# main_board.net
KiCad netlist of a schematic drawn in Altium Designer
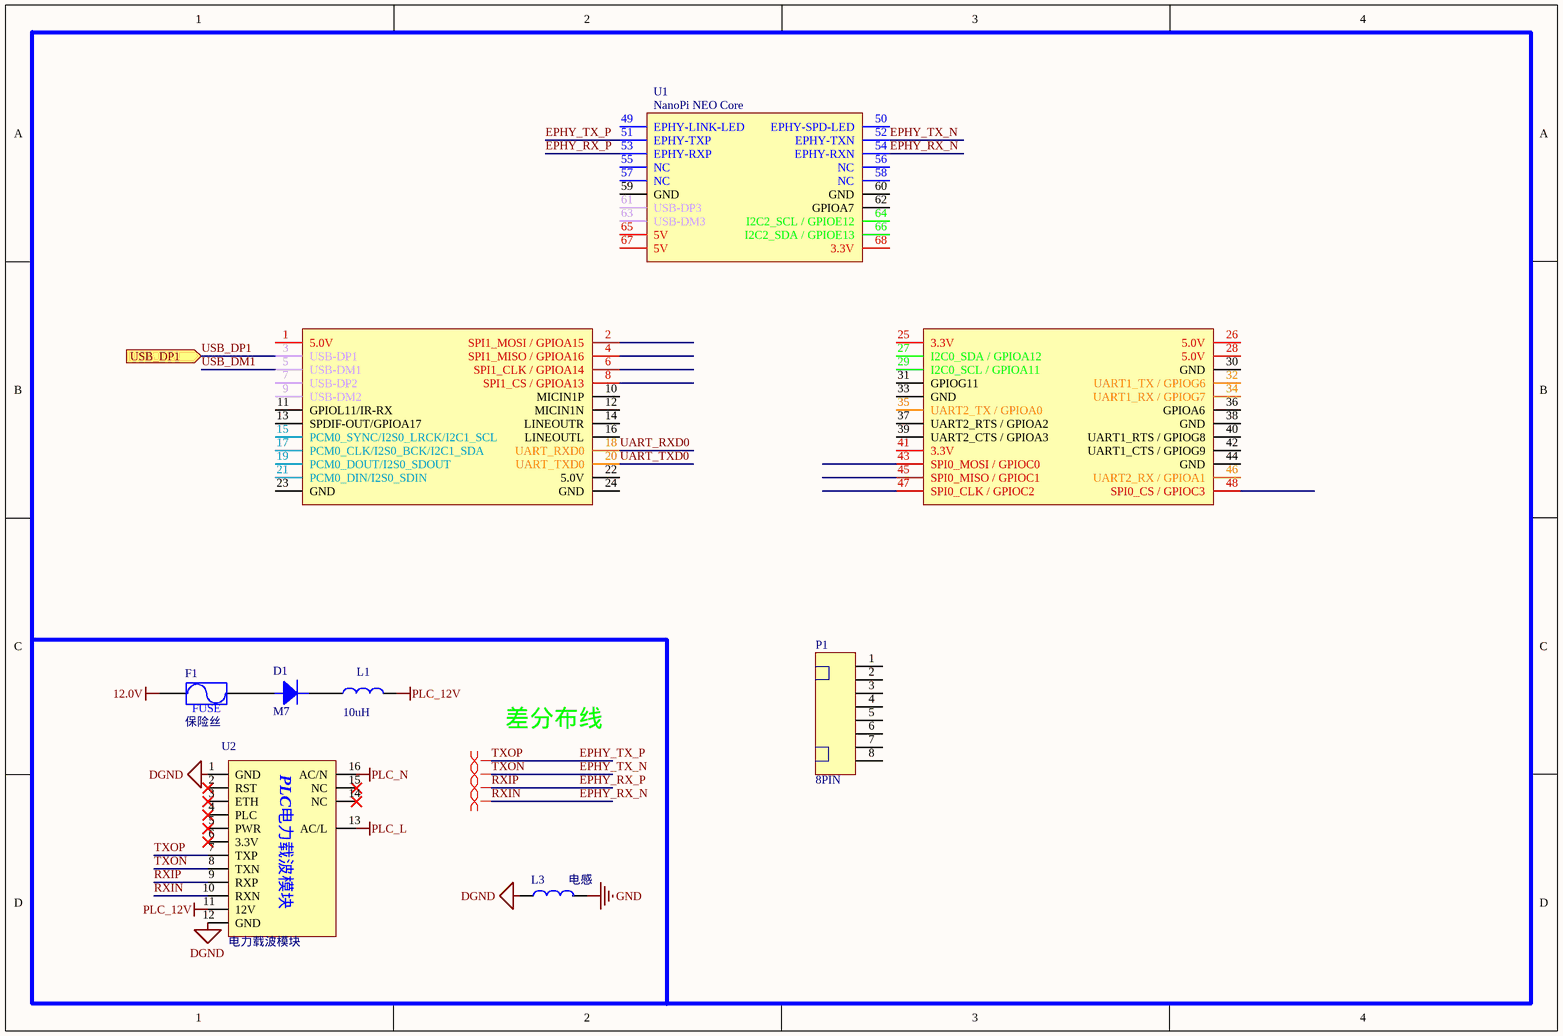
[diagram p0: main_board.SchDoc]

(export (version "E")
  (design (tool "Eeschema 10.0.6"))
  (components
    (comp (ref "D1")
      (value "M7")
      (footprint "SMA/DO-214AC")
      (description "二极管")
      (libsource (lib "集大电协1.5") (part "Diode"))
    )
    (comp (ref "F1") (value "保险丝") (footprint "FUSE-1206") (libsource (lib "集大电协1.2") (part "Fuse")))
    (comp (ref "L1")
      (value "10uH")
      (footprint "1206L")
      (description "电感")
      (libsource (lib "集大电协1.5") (part "L"))
    )
    (comp (ref "L3") (value "电感") (footprint "1206L") (libsource (lib "集大电协1.5") (part "L")))
    (comp (ref "P1") (value "8PIN") (footprint "MX1.25WS-8P") (libsource (lib "MX") (part "MX1.25-8P")))
    (comp (ref "U1")
      (value "NanoPi NEO Core")
      (footprint "NanoPi NEO Core")
      (libsource (lib "集大电协1.5") (part "NanoPi NEO Core"))
    )
    (comp (ref "U2")
      (value "电力载波模块")
      (footprint "电力载波模块6410")
      (libsource (lib "集大电协1.2") (part "电力载波模块6410"))
    )
  )
  (nets
    (net (code "1") (name "/EPHY_RX_N") (class "Default")
      (node (ref "U1") (pin "54") (pinfunction "EPHY-RXN_54") (pintype "passive"))
      (node (ref "U2") (pin "10") (pinfunction "RXN_10") (pintype "passive"))
    )
    (net (code "2") (name "/EPHY_RX_P") (class "Default")
      (node (ref "U1") (pin "53") (pinfunction "EPHY-RXP_53") (pintype "passive"))
      (node (ref "U2") (pin "9") (pinfunction "RXP_9") (pintype "passive"))
    )
    (net (code "3") (name "/EPHY_TX_N") (class "Default")
      (node (ref "U1") (pin "52") (pinfunction "EPHY-TXN_52") (pintype "passive"))
      (node (ref "U2") (pin "8") (pinfunction "TXN_8") (pintype "passive"))
    )
    (net (code "4") (name "/EPHY_TX_P") (class "Default")
      (node (ref "U1") (pin "51") (pinfunction "EPHY-TXP_51") (pintype "passive"))
      (node (ref "U2") (pin "7") (pinfunction "TXP_7") (pintype "passive"))
    )
    (net (code "5") (name "/UART_RXD0") (class "Default")
      (node (ref "U1") (pin "18") (pinfunction "UART_RXD0_18") (pintype "passive"))
    )
    (net (code "6") (name "/UART_TXD0") (class "Default")
      (node (ref "U1") (pin "20") (pinfunction "UART_TXD0_20") (pintype "passive"))
    )
    (net (code "7") (name "/USB_DM1") (class "Default")
      (node (ref "U1") (pin "5") (pinfunction "USB-DM1_5") (pintype "passive"))
    )
    (net (code "8") (name "/USB_DP1") (class "Default")
      (node (ref "U1") (pin "3") (pinfunction "USB-DP1_3") (pintype "passive"))
    )
    (net (code "9") (name "12.0V") (class "Default")
      (node (ref "F1") (pin "1") (pinfunction "1_1") (pintype "passive"))
    )
    (net (code "10") (name "DGND") (class "Default")
      (node (ref "L3") (pin "1") (pinfunction "1_1") (pintype "passive"))
      (node (ref "U2") (pin "1") (pinfunction "GND_1") (pintype "passive"))
      (node (ref "U2") (pin "12") (pinfunction "GND_12") (pintype "passive"))
    )
    (net (code "11") (name "GND") (class "Default")
      (node (ref "L3") (pin "2") (pinfunction "2_2") (pintype "passive"))
    )
    (net (code "12") (name "Net-(D1-Pad1)") (class "Default")
      (node (ref "D1") (pin "1") (pintype "passive"))
      (node (ref "F1") (pin "2") (pinfunction "2_2") (pintype "passive"))
    )
    (net (code "13") (name "Net-(D1-Pad2)") (class "Default")
      (node (ref "D1") (pin "2") (pinfunction "2_2") (pintype "passive"))
      (node (ref "L1") (pin "1") (pinfunction "1_1") (pintype "passive"))
    )
    (net (code "14") (name "PLC_12V") (class "Default")
      (node (ref "L1") (pin "2") (pinfunction "2_2") (pintype "passive"))
      (node (ref "U2") (pin "11") (pinfunction "12V_11") (pintype "passive"))
    )
    (net (code "15") (name "PLC_L") (class "Default")
      (node (ref "U2") (pin "13") (pinfunction "AC/L_13") (pintype "passive"))
    )
    (net (code "16") (name "PLC_N") (class "Default")
      (node (ref "U2") (pin "16") (pinfunction "AC/N_16") (pintype "passive"))
    )
    (net (code "17") (name "unconnected-(P1-Pad1)") (class "Default")
      (node (ref "P1") (pin "1") (pinfunction "1_1") (pintype "passive"))
    )
    (net (code "18") (name "unconnected-(P1-Pad2)") (class "Default")
      (node (ref "P1") (pin "2") (pinfunction "2_2") (pintype "passive"))
    )
    (net (code "19") (name "unconnected-(P1-Pad3)") (class "Default")
      (node (ref "P1") (pin "3") (pinfunction "3_3") (pintype "passive"))
    )
    (net (code "20") (name "unconnected-(P1-Pad4)") (class "Default")
      (node (ref "P1") (pin "4") (pinfunction "4_4") (pintype "passive"))
    )
    (net (code "21") (name "unconnected-(P1-Pad5)") (class "Default")
      (node (ref "P1") (pin "5") (pinfunction "5_5") (pintype "passive"))
    )
    (net (code "22") (name "unconnected-(P1-Pad6)") (class "Default")
      (node (ref "P1") (pin "6") (pinfunction "6_6") (pintype "passive"))
    )
    (net (code "23") (name "unconnected-(P1-Pad7)") (class "Default")
      (node (ref "P1") (pin "7") (pinfunction "7_7") (pintype "passive"))
    )
    (net (code "24") (name "unconnected-(P1-Pad8)") (class "Default")
      (node (ref "P1") (pin "8") (pinfunction "8_8") (pintype "passive"))
    )
    (net (code "25") (name "unconnected-(U1-3.3V-Pad25)") (class "Default")
      (node (ref "U1") (pin "25") (pinfunction "3.3V_25") (pintype "passive"))
    )
    (net (code "26") (name "unconnected-(U1-3.3V-Pad41)") (class "Default")
      (node (ref "U1") (pin "41") (pinfunction "3.3V_41") (pintype "passive"))
    )
    (net (code "27") (name "unconnected-(U1-3.3V-Pad68)") (class "Default")
      (node (ref "U1") (pin "68") (pinfunction "3.3V_68") (pintype "passive"))
    )
    (net (code "28") (name "unconnected-(U1-5.0V-Pad1)") (class "Default")
      (node (ref "U1") (pin "1") (pinfunction "5.0V_1") (pintype "passive"))
    )
    (net (code "29") (name "unconnected-(U1-5.0V-Pad22)") (class "Default")
      (node (ref "U1") (pin "22") (pinfunction "5.0V_22") (pintype "passive"))
    )
    (net (code "30") (name "unconnected-(U1-5.0V-Pad26)") (class "Default")
      (node (ref "U1") (pin "26") (pinfunction "5.0V_26") (pintype "passive"))
    )
    (net (code "31") (name "unconnected-(U1-5.0V-Pad28)") (class "Default")
      (node (ref "U1") (pin "28") (pinfunction "5.0V_28") (pintype "passive"))
    )
    (net (code "32") (name "unconnected-(U1-5V-Pad65)") (class "Default")
      (node (ref "U1") (pin "65") (pinfunction "5V_65") (pintype "passive"))
    )
    (net (code "33") (name "unconnected-(U1-5V-Pad67)") (class "Default")
      (node (ref "U1") (pin "67") (pinfunction "5V_67") (pintype "passive"))
    )
    (net (code "34") (name "unconnected-(U1-EPHY-LINK-LED-Pad49)") (class "Default")
      (node (ref "U1") (pin "49") (pinfunction "EPHY-LINK-LED_49") (pintype "passive"))
    )
    (net (code "35") (name "unconnected-(U1-EPHY-SPD-LED-Pad50)") (class "Default")
      (node (ref "U1") (pin "50") (pinfunction "EPHY-SPD-LED_50") (pintype "passive"))
    )
    (net (code "36") (name "unconnected-(U1-GND-Pad23)") (class "Default")
      (node (ref "U1") (pin "23") (pinfunction "GND_23") (pintype "passive"))
    )
    (net (code "37") (name "unconnected-(U1-GND-Pad24)") (class "Default")
      (node (ref "U1") (pin "24") (pinfunction "GND_24") (pintype "passive"))
    )
    (net (code "38") (name "unconnected-(U1-GND-Pad30)") (class "Default")
      (node (ref "U1") (pin "30") (pinfunction "GND_30") (pintype "passive"))
    )
    (net (code "39") (name "unconnected-(U1-GND-Pad33)") (class "Default")
      (node (ref "U1") (pin "33") (pinfunction "GND_33") (pintype "passive"))
    )
    (net (code "40") (name "unconnected-(U1-GND-Pad38)") (class "Default")
      (node (ref "U1") (pin "38") (pinfunction "GND_38") (pintype "passive"))
    )
    (net (code "41") (name "unconnected-(U1-GND-Pad44)") (class "Default")
      (node (ref "U1") (pin "44") (pinfunction "GND_44") (pintype "passive"))
    )
    (net (code "42") (name "unconnected-(U1-GND-Pad59)") (class "Default")
      (node (ref "U1") (pin "59") (pinfunction "GND_59") (pintype "passive"))
    )
    (net (code "43") (name "unconnected-(U1-GND-Pad60)") (class "Default")
      (node (ref "U1") (pin "60") (pinfunction "GND_60") (pintype "passive"))
    )
    (net (code "44") (name "unconnected-(U1-GPIOA6-Pad36)") (class "Default")
      (node (ref "U1") (pin "36") (pinfunction "GPIOA6_36") (pintype "passive"))
    )
    (net (code "45") (name "unconnected-(U1-GPIOA7-Pad62)") (class "Default")
      (node (ref "U1") (pin "62") (pinfunction "GPIOA7_62") (pintype "passive"))
    )
    (net (code "46") (name "unconnected-(U1-GPIOG11-Pad31)") (class "Default")
      (node (ref "U1") (pin "31") (pinfunction "GPIOG11_31") (pintype "passive"))
    )
    (net (code "47") (name "unconnected-(U1-GPIOL11{slash}IR-RX-Pad11)") (class "Default")
      (node (ref "U1") (pin "11") (pinfunction "GPIOL11/IR-RX_11") (pintype "passive"))
    )
    (net (code "48") (name "unconnected-(U1-I2C0_SCL_{slash}_GPIOA11-Pad29)") (class "Default")
      (node (ref "U1") (pin "29") (pinfunction "I2C0_SCL_/_GPIOA11_29") (pintype "passive"))
    )
    (net (code "49") (name "unconnected-(U1-I2C0_SDA_{slash}_GPIOA12-Pad27)") (class "Default")
      (node (ref "U1") (pin "27") (pinfunction "I2C0_SDA_/_GPIOA12_27") (pintype "passive"))
    )
    (net (code "50") (name "unconnected-(U1-I2C2_SCL_{slash}_GPIOE12-Pad64)") (class "Default")
      (node (ref "U1") (pin "64") (pinfunction "I2C2_SCL_/_GPIOE12_64") (pintype "passive"))
    )
    (net (code "51") (name "unconnected-(U1-I2C2_SDA_{slash}_GPIOE13-Pad66)") (class "Default")
      (node (ref "U1") (pin "66") (pinfunction "I2C2_SDA_/_GPIOE13_66") (pintype "passive"))
    )
    (net (code "52") (name "unconnected-(U1-LINEOUTL-Pad16)") (class "Default")
      (node (ref "U1") (pin "16") (pinfunction "LINEOUTL_16") (pintype "passive"))
    )
    (net (code "53") (name "unconnected-(U1-LINEOUTR-Pad14)") (class "Default")
      (node (ref "U1") (pin "14") (pinfunction "LINEOUTR_14") (pintype "passive"))
    )
    (net (code "54") (name "unconnected-(U1-MICIN1N-Pad12)") (class "Default")
      (node (ref "U1") (pin "12") (pinfunction "MICIN1N_12") (pintype "passive"))
    )
    (net (code "55") (name "unconnected-(U1-MICIN1P-Pad10)") (class "Default")
      (node (ref "U1") (pin "10") (pinfunction "MICIN1P_10") (pintype "passive"))
    )
    (net (code "56") (name "unconnected-(U1-NC-Pad55)") (class "Default")
      (node (ref "U1") (pin "55") (pinfunction "NC_55") (pintype "passive"))
    )
    (net (code "57") (name "unconnected-(U1-NC-Pad56)") (class "Default")
      (node (ref "U1") (pin "56") (pinfunction "NC_56") (pintype "passive"))
    )
    (net (code "58") (name "unconnected-(U1-NC-Pad57)") (class "Default")
      (node (ref "U1") (pin "57") (pinfunction "NC_57") (pintype "passive"))
    )
    (net (code "59") (name "unconnected-(U1-NC-Pad58)") (class "Default")
      (node (ref "U1") (pin "58") (pinfunction "NC_58") (pintype "passive"))
    )
    (net (code "60") (name "unconnected-(U1-PCM0_CLK{slash}I2S0_BCK{slash}I2C1_SDA-Pad17)") (class "Default")
      (node (ref "U1") (pin "17") (pinfunction "PCM0_CLK/I2S0_BCK/I2C1_SDA_17") (pintype "passive"))
    )
    (net (code "61") (name "unconnected-(U1-PCM0_DIN{slash}I2S0_SDIN-Pad21)") (class "Default")
      (node (ref "U1") (pin "21") (pinfunction "PCM0_DIN/I2S0_SDIN_21") (pintype "passive"))
    )
    (net (code "62") (name "unconnected-(U1-PCM0_DOUT{slash}I2S0_SDOUT-Pad19)") (class "Default")
      (node (ref "U1") (pin "19") (pinfunction "PCM0_DOUT/I2S0_SDOUT_19") (pintype "passive"))
    )
    (net (code "63") (name "unconnected-(U1-PCM0_SYNC{slash}I2S0_LRCK{slash}I2C1_SCL-Pad15)") (class "Default")
      (node (ref "U1") (pin "15") (pinfunction "PCM0_SYNC/I2S0_LRCK/I2C1_SCL_15") (pintype "passive"))
    )
    (net (code "64") (name "unconnected-(U1-SPDIF-OUT{slash}GPIOA17-Pad13)") (class "Default")
      (node (ref "U1") (pin "13") (pinfunction "SPDIF-OUT/GPIOA17_13") (pintype "passive"))
    )
    (net (code "65") (name "unconnected-(U1-SPI0_CLK_{slash}_GPIOC2-Pad47)") (class "Default")
      (node (ref "U1") (pin "47") (pinfunction "SPI0_CLK_/_GPIOC2_47") (pintype "passive"))
    )
    (net (code "66") (name "unconnected-(U1-SPI0_CS_{slash}_GPIOC3-Pad48)") (class "Default")
      (node (ref "U1") (pin "48") (pinfunction "SPI0_CS_/_GPIOC3_48") (pintype "passive"))
    )
    (net (code "67") (name "unconnected-(U1-SPI0_MISO_{slash}_GPIOC1-Pad45)") (class "Default")
      (node (ref "U1") (pin "45") (pinfunction "SPI0_MISO_/_GPIOC1_45") (pintype "passive"))
    )
    (net (code "68") (name "unconnected-(U1-SPI0_MOSI_{slash}_GPIOC0-Pad43)") (class "Default")
      (node (ref "U1") (pin "43") (pinfunction "SPI0_MOSI_/_GPIOC0_43") (pintype "passive"))
    )
    (net (code "69") (name "unconnected-(U1-SPI1_CLK_{slash}_GPIOA14-Pad6)") (class "Default")
      (node (ref "U1") (pin "6") (pinfunction "SPI1_CLK_/_GPIOA14_6") (pintype "passive"))
    )
    (net (code "70") (name "unconnected-(U1-SPI1_CS_{slash}_GPIOA13-Pad8)") (class "Default")
      (node (ref "U1") (pin "8") (pinfunction "SPI1_CS_/_GPIOA13_8") (pintype "passive"))
    )
    (net (code "71") (name "unconnected-(U1-SPI1_MISO_{slash}_GPIOA16-Pad4)") (class "Default")
      (node (ref "U1") (pin "4") (pinfunction "SPI1_MISO_/_GPIOA16_4") (pintype "passive"))
    )
    (net (code "72") (name "unconnected-(U1-SPI1_MOSI_{slash}_GPIOA15-Pad2)") (class "Default")
      (node (ref "U1") (pin "2") (pinfunction "SPI1_MOSI_/_GPIOA15_2") (pintype "passive"))
    )
    (net (code "73") (name "unconnected-(U1-UART1_CTS_{slash}_GPIOG9-Pad42)") (class "Default")
      (node (ref "U1") (pin "42") (pinfunction "UART1_CTS_/_GPIOG9_42") (pintype "passive"))
    )
    (net (code "74") (name "unconnected-(U1-UART1_RTS_{slash}_GPIOG8-Pad40)") (class "Default")
      (node (ref "U1") (pin "40") (pinfunction "UART1_RTS_/_GPIOG8_40") (pintype "passive"))
    )
    (net (code "75") (name "unconnected-(U1-UART1_RX_{slash}_GPIOG7-Pad34)") (class "Default")
      (node (ref "U1") (pin "34") (pinfunction "UART1_RX_/_GPIOG7_34") (pintype "passive"))
    )
    (net (code "76") (name "unconnected-(U1-UART1_TX_{slash}_GPIOG6-Pad32)") (class "Default")
      (node (ref "U1") (pin "32") (pinfunction "UART1_TX_/_GPIOG6_32") (pintype "passive"))
    )
    (net (code "77") (name "unconnected-(U1-UART2_CTS_{slash}_GPIOA3-Pad39)") (class "Default")
      (node (ref "U1") (pin "39") (pinfunction "UART2_CTS_/_GPIOA3_39") (pintype "passive"))
    )
    (net (code "78") (name "unconnected-(U1-UART2_RTS_{slash}_GPIOA2-Pad37)") (class "Default")
      (node (ref "U1") (pin "37") (pinfunction "UART2_RTS_/_GPIOA2_37") (pintype "passive"))
    )
    (net (code "79") (name "unconnected-(U1-UART2_RX_{slash}_GPIOA1-Pad46)") (class "Default")
      (node (ref "U1") (pin "46") (pinfunction "UART2_RX_/_GPIOA1_46") (pintype "passive"))
    )
    (net (code "80") (name "unconnected-(U1-UART2_TX_{slash}_GPIOA0-Pad35)") (class "Default")
      (node (ref "U1") (pin "35") (pinfunction "UART2_TX_/_GPIOA0_35") (pintype "passive"))
    )
    (net (code "81") (name "unconnected-(U1-USB-DM2-Pad9)") (class "Default")
      (node (ref "U1") (pin "9") (pinfunction "USB-DM2_9") (pintype "passive"))
    )
    (net (code "82") (name "unconnected-(U1-USB-DM3-Pad63)") (class "Default")
      (node (ref "U1") (pin "63") (pinfunction "USB-DM3_63") (pintype "passive"))
    )
    (net (code "83") (name "unconnected-(U1-USB-DP2-Pad7)") (class "Default")
      (node (ref "U1") (pin "7") (pinfunction "USB-DP2_7") (pintype "passive"))
    )
    (net (code "84") (name "unconnected-(U1-USB-DP3-Pad61)") (class "Default")
      (node (ref "U1") (pin "61") (pinfunction "USB-DP3_61") (pintype "passive"))
    )
    (net (code "85") (name "unconnected-(U2-3.3V-Pad6)") (class "Default")
      (node (ref "U2") (pin "6") (pinfunction "3.3V_6") (pintype "passive+no_connect"))
    )
    (net (code "86") (name "unconnected-(U2-ETH-Pad3)") (class "Default")
      (node (ref "U2") (pin "3") (pinfunction "ETH_3") (pintype "passive+no_connect"))
    )
    (net (code "87") (name "unconnected-(U2-NC-Pad14)") (class "Default")
      (node (ref "U2") (pin "14") (pinfunction "NC_14") (pintype "passive+no_connect"))
    )
    (net (code "88") (name "unconnected-(U2-NC-Pad15)") (class "Default")
      (node (ref "U2") (pin "15") (pinfunction "NC_15") (pintype "passive+no_connect"))
    )
    (net (code "89") (name "unconnected-(U2-PLC-Pad4)") (class "Default")
      (node (ref "U2") (pin "4") (pinfunction "PLC_4") (pintype "passive+no_connect"))
    )
    (net (code "90") (name "unconnected-(U2-PWR-Pad5)") (class "Default")
      (node (ref "U2") (pin "5") (pinfunction "PWR_5") (pintype "passive+no_connect"))
    )
    (net (code "91") (name "unconnected-(U2-RST-Pad2)") (class "Default")
      (node (ref "U2") (pin "2") (pinfunction "RST_2") (pintype "passive+no_connect"))
    )
  )
)
